# relay_board.net
KiCad netlist of a schematic drawn in EAGLE
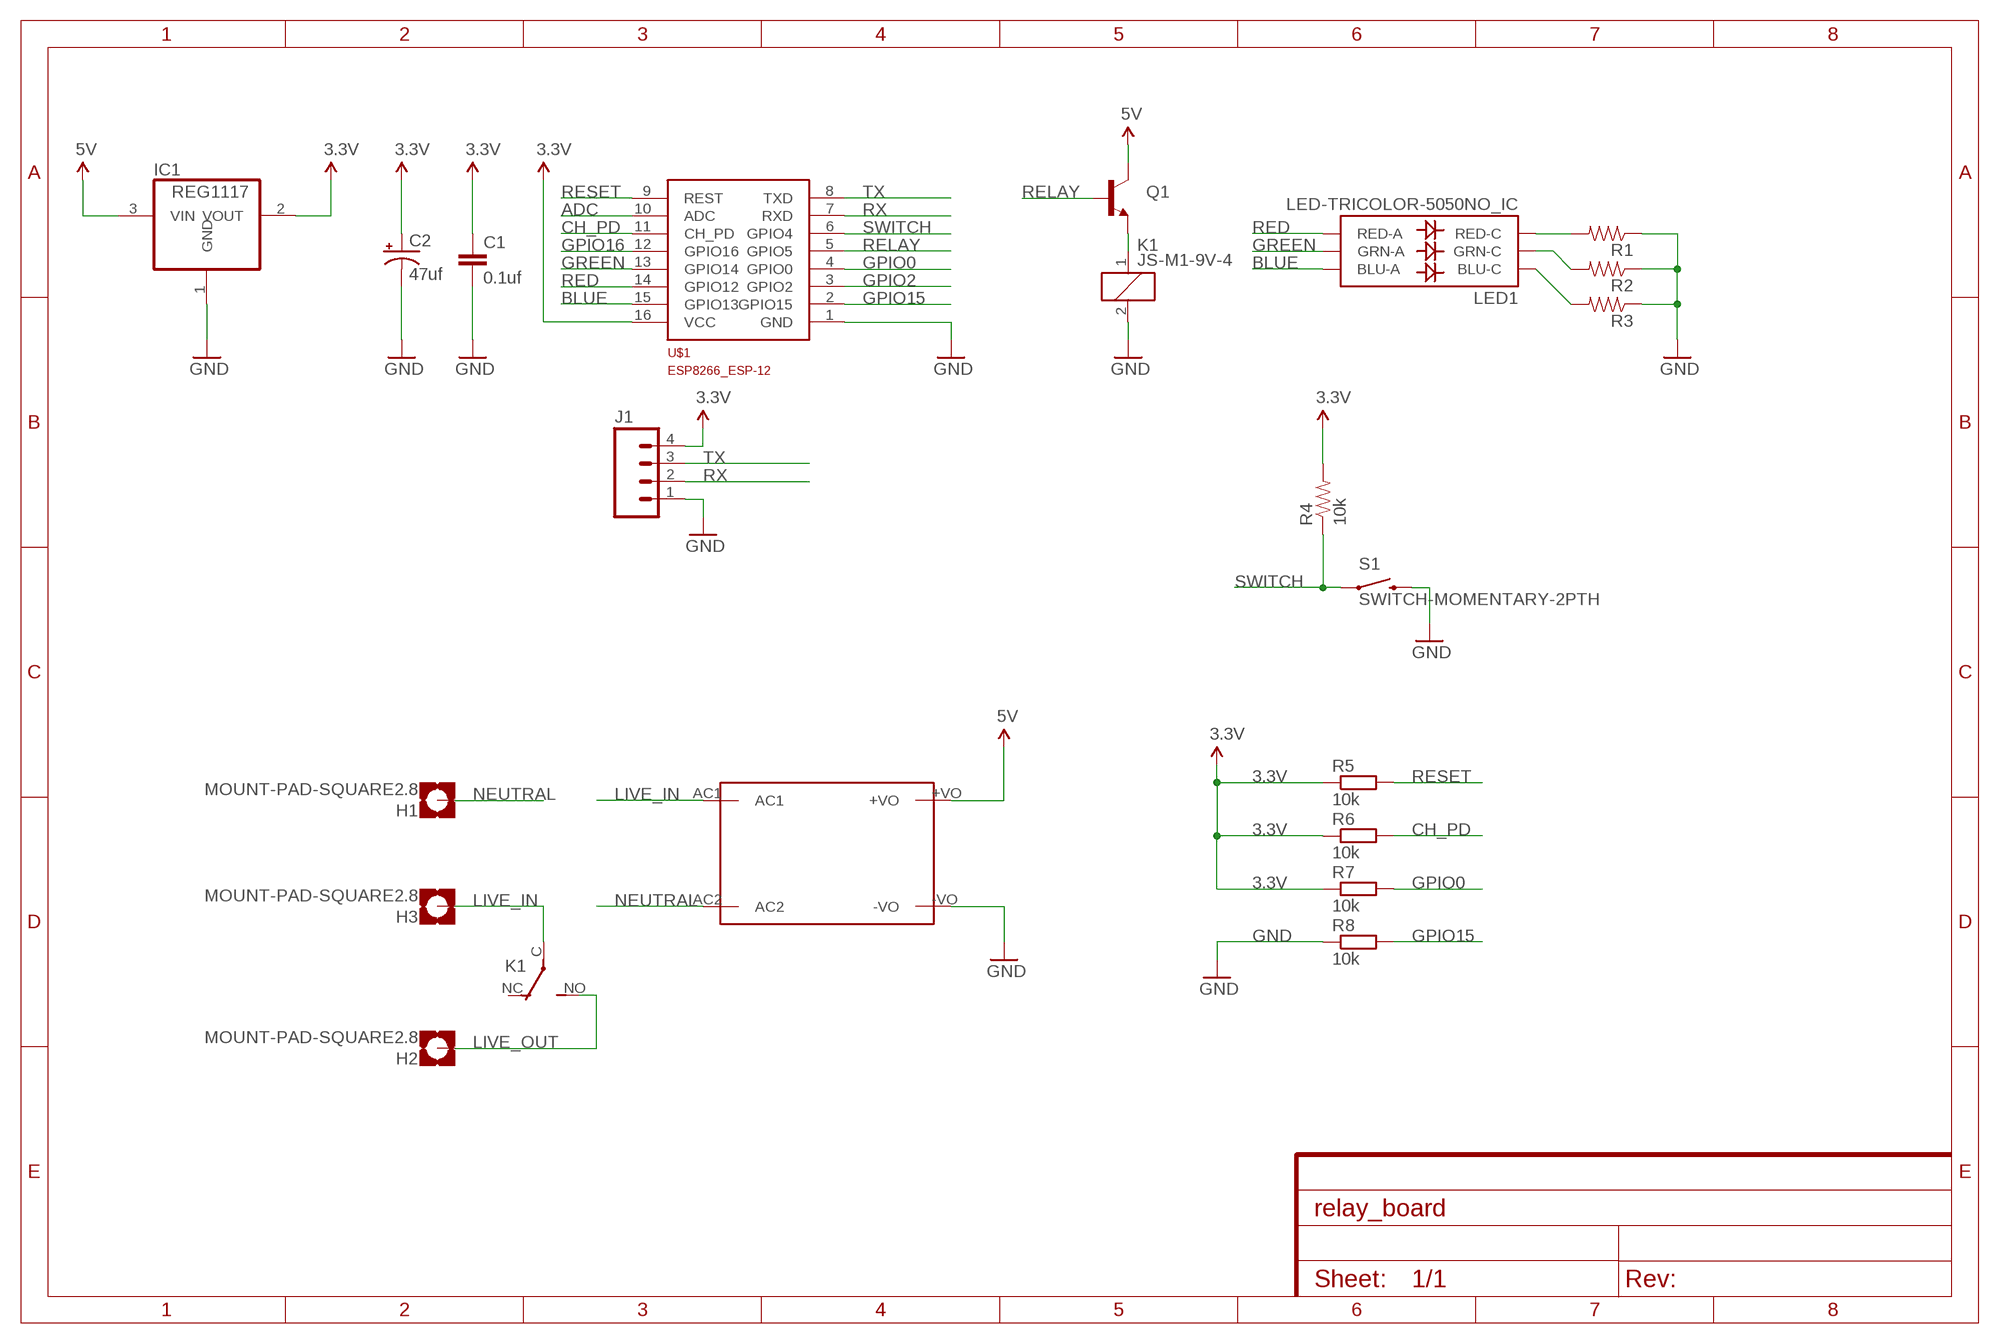
[diagram p0: schematic, sheet 1]

(export (version "E")
  (design (tool "Eeschema 10.0.6"))
  (components
    (comp (ref "C1")
      (value "0.1uf")
      (footprint "eagle-import:0805")
      (libsource (lib "eagle-import") (part "CAP0805"))
    )
    (comp (ref "C2")
      (value "47uf")
      (footprint "eagle-import:PANASONIC_E")
      (libsource (lib "eagle-import") (part "CAP_POLE"))
    )
    (comp (ref "H1")
      (value "MOUNT-PAD-SQUARE2.8")
      (footprint "eagle-import:2,8-PAD-SQUARE")
      (libsource (lib "eagle-import") (part "MOUNT-PAD-SQUARE2.8"))
    )
    (comp (ref "H2")
      (value "MOUNT-PAD-SQUARE2.8")
      (footprint "eagle-import:2,8-PAD-SQUARE")
      (libsource (lib "eagle-import") (part "MOUNT-PAD-SQUARE2.8"))
    )
    (comp (ref "H3")
      (value "MOUNT-PAD-SQUARE2.8")
      (footprint "eagle-import:2,8-PAD-SQUARE")
      (libsource (lib "eagle-import") (part "MOUNT-PAD-SQUARE2.8"))
    )
    (comp (ref "IC1")
      (value "REG1117")
      (footprint "eagle-import:SOT223")
      (libsource (lib "eagle-import") (part "REG1117"))
    )
    (comp (ref "J1")
      (value "M04LOCK")
      (footprint "eagle-import:1X04_LOCK")
      (libsource (lib "eagle-import") (part "M04LOCK"))
    )
    (comp (ref "K1")
      (value "JS-M1-9V-4")
      (footprint "eagle-import:JS-M")
      (libsource (lib "eagle-import") (part "JS-M1-9V-4"))
    )
    (comp (ref "LED1")
      (value "LED-TRICOLOR-5050NO_IC")
      (footprint "eagle-import:LED-TRICOLOR-5050")
      (libsource (lib "eagle-import") (part "LED-TRICOLOR-5050NO_IC"))
    )
    (comp (ref "Q1")
      (value "TRANSISTOR_NPNSMD2")
      (footprint "eagle-import:SOT223")
      (libsource (lib "eagle-import") (part "TRANSISTOR_NPNSMD2"))
    )
    (comp (ref "R1")
      (value "RESISTOR0805-RES")
      (footprint "eagle-import:0805")
      (libsource (lib "eagle-import") (part "RESISTOR0805-RES"))
    )
    (comp (ref "R2")
      (value "RESISTOR0805-RES")
      (footprint "eagle-import:0805")
      (libsource (lib "eagle-import") (part "RESISTOR0805-RES"))
    )
    (comp (ref "R3")
      (value "RESISTOR0805-RES")
      (footprint "eagle-import:0805")
      (libsource (lib "eagle-import") (part "RESISTOR0805-RES"))
    )
    (comp (ref "R4")
      (value "10k")
      (footprint "eagle-import:0805")
      (libsource (lib "eagle-import") (part "RESISTOR0805-RES"))
    )
    (comp (ref "R5")
      (value "10k")
      (footprint "eagle-import:R0805")
      (libsource (lib "eagle-import") (part "R-EU_R0805"))
    )
    (comp (ref "R6")
      (value "10k")
      (footprint "eagle-import:R0805")
      (libsource (lib "eagle-import") (part "R-EU_R0805"))
    )
    (comp (ref "R7")
      (value "10k")
      (footprint "eagle-import:R0805")
      (libsource (lib "eagle-import") (part "R-EU_R0805"))
    )
    (comp (ref "R8")
      (value "10k")
      (footprint "eagle-import:R0805")
      (libsource (lib "eagle-import") (part "R-EU_R0805"))
    )
    (comp (ref "S1")
      (value "SWITCH-MOMENTARY-2PTH")
      (footprint "eagle-import:TACTILE-PTH")
      (libsource (lib "eagle-import") (part "SWITCH-MOMENTARY-2PTH"))
    )
    (comp (ref "U$1")
      (value "ESP8266_ESP-12")
      (footprint "eagle-import:ESP8266-ESP12")
      (libsource (lib "eagle-import") (part "ESP8266_ESP-12"))
    )
    (comp (ref "U$2")
      (value "HLK-PM03")
      (footprint "eagle-import:HLK-PM03")
      (libsource (lib "eagle-import") (part "HLK-PM03"))
    )
  )
  (nets
    (net (code "1") (name "/ADC") (class "Default")
      (node (ref "U$1") (pin "10") (pinfunction "ADC_10") (pintype "bidirectional"))
    )
    (net (code "2") (name "/BLUE") (class "Default")
      (node (ref "LED1") (pin "3") (pinfunction "BLU-A_3") (pintype "bidirectional"))
      (node (ref "U$1") (pin "15") (pinfunction "GPIO13_15") (pintype "bidirectional"))
    )
    (net (code "3") (name "/CH_PD") (class "Default")
      (node (ref "R6") (pin "2") (pinfunction "2_2") (pintype "passive"))
      (node (ref "U$1") (pin "11") (pinfunction "CH_PD_11") (pintype "bidirectional"))
    )
    (net (code "4") (name "/GPIO0") (class "Default")
      (node (ref "R7") (pin "2") (pinfunction "2_2") (pintype "passive"))
      (node (ref "U$1") (pin "4") (pinfunction "GPIO0_4") (pintype "bidirectional"))
    )
    (net (code "5") (name "/GPIO2") (class "Default")
      (node (ref "U$1") (pin "3") (pinfunction "GPIO2_3") (pintype "bidirectional"))
    )
    (net (code "6") (name "/GPIO15") (class "Default")
      (node (ref "R8") (pin "2") (pinfunction "2_2") (pintype "passive"))
      (node (ref "U$1") (pin "2") (pinfunction "GPIO15_2") (pintype "bidirectional"))
    )
    (net (code "7") (name "/GPIO16") (class "Default")
      (node (ref "U$1") (pin "12") (pinfunction "GPIO16_12") (pintype "bidirectional"))
    )
    (net (code "8") (name "/GREEN") (class "Default")
      (node (ref "LED1") (pin "1") (pinfunction "GRN-A_1") (pintype "bidirectional"))
      (node (ref "U$1") (pin "13") (pinfunction "GPIO14_13") (pintype "bidirectional"))
    )
    (net (code "9") (name "/LIVE_IN") (class "Default")
      (node (ref "H3") (pin "B2,8") (pinfunction "MOUNT_B2,8") (pintype "passive"))
      (node (ref "K1") (pin "C") (pinfunction "P_C") (pintype "passive"))
      (node (ref "U$2") (pin "AC1") (pinfunction "AC1_AC1") (pintype "bidirectional"))
    )
    (net (code "10") (name "/LIVE_OUT") (class "Default")
      (node (ref "H2") (pin "B2,8") (pinfunction "MOUNT_B2,8") (pintype "passive"))
      (node (ref "K1") (pin "NO") (pinfunction "S_NO") (pintype "passive"))
    )
    (net (code "11") (name "/NEUTRAL") (class "Default")
      (node (ref "H1") (pin "B2,8") (pinfunction "MOUNT_B2,8") (pintype "passive"))
      (node (ref "U$2") (pin "AC2") (pinfunction "AC2_AC2") (pintype "bidirectional"))
    )
    (net (code "12") (name "/RED") (class "Default")
      (node (ref "LED1") (pin "2") (pinfunction "RED-A_2") (pintype "bidirectional"))
      (node (ref "U$1") (pin "14") (pinfunction "GPIO12_14") (pintype "bidirectional"))
    )
    (net (code "13") (name "/RELAY") (class "Default")
      (node (ref "Q1") (pin "1") (pinfunction "B_1") (pintype "passive"))
      (node (ref "U$1") (pin "5") (pinfunction "GPIO5_5") (pintype "bidirectional"))
    )
    (net (code "14") (name "/RESET") (class "Default")
      (node (ref "R5") (pin "2") (pinfunction "2_2") (pintype "passive"))
      (node (ref "U$1") (pin "9") (pinfunction "REST_9") (pintype "bidirectional"))
    )
    (net (code "15") (name "/RX") (class "Default")
      (node (ref "J1") (pin "2") (pinfunction "2_2") (pintype "passive"))
      (node (ref "U$1") (pin "7") (pinfunction "RXD_7") (pintype "bidirectional"))
    )
    (net (code "16") (name "/SWITCH") (class "Default")
      (node (ref "R4") (pin "1") (pinfunction "1_1") (pintype "passive"))
      (node (ref "S1") (pin "1") (pinfunction "1_1") (pintype "passive"))
      (node (ref "U$1") (pin "6") (pinfunction "GPIO4_6") (pintype "bidirectional"))
    )
    (net (code "17") (name "/TX") (class "Default")
      (node (ref "J1") (pin "3") (pinfunction "3_3") (pintype "passive"))
      (node (ref "U$1") (pin "8") (pinfunction "TXD_8") (pintype "bidirectional"))
    )
    (net (code "18") (name "3.3V") (class "Default")
      (node (ref "C1") (pin "1") (pinfunction "1_1") (pintype "passive"))
      (node (ref "C2") (pin "+") (pinfunction "+_+") (pintype "passive"))
      (node (ref "IC1") (pin "2") (pinfunction "VOUT_2") (pintype "output"))
      (node (ref "J1") (pin "4") (pinfunction "4_4") (pintype "passive"))
      (node (ref "R4") (pin "2") (pinfunction "2_2") (pintype "passive"))
      (node (ref "R5") (pin "1") (pinfunction "1_1") (pintype "passive"))
      (node (ref "R6") (pin "1") (pinfunction "1_1") (pintype "passive"))
      (node (ref "R7") (pin "1") (pinfunction "1_1") (pintype "passive"))
      (node (ref "U$1") (pin "16") (pinfunction "VCC_16") (pintype "bidirectional"))
    )
    (net (code "19") (name "5V") (class "Default")
      (node (ref "IC1") (pin "3") (pinfunction "VIN_3") (pintype "input"))
      (node (ref "Q1") (pin "2") (pinfunction "C_2") (pintype "passive"))
      (node (ref "U$2") (pin "+VO") (pinfunction "+VO_+VO") (pintype "bidirectional"))
    )
    (net (code "20") (name "GND") (class "Default")
      (node (ref "C1") (pin "2") (pinfunction "2_2") (pintype "passive"))
      (node (ref "C2") (pin "-") (pinfunction "-_-") (pintype "passive"))
      (node (ref "IC1") (pin "1") (pinfunction "GND_1") (pintype "power_in"))
      (node (ref "J1") (pin "1") (pinfunction "1_1") (pintype "passive"))
      (node (ref "K1") (pin "2") (pinfunction "2_2") (pintype "passive"))
      (node (ref "R1") (pin "1") (pinfunction "1_1") (pintype "passive"))
      (node (ref "R2") (pin "1") (pinfunction "1_1") (pintype "passive"))
      (node (ref "R3") (pin "1") (pinfunction "1_1") (pintype "passive"))
      (node (ref "R8") (pin "1") (pinfunction "1_1") (pintype "passive"))
      (node (ref "S1") (pin "3") (pinfunction "2_3") (pintype "passive"))
      (node (ref "U$1") (pin "1") (pinfunction "GND_1") (pintype "bidirectional"))
      (node (ref "U$2") (pin "-VO") (pinfunction "-VO_-VO") (pintype "bidirectional"))
    )
    (net (code "21") (name "Net-(LED1-BLU-C)") (class "Default")
      (node (ref "LED1") (pin "4") (pinfunction "BLU-C_4") (pintype "bidirectional"))
      (node (ref "R3") (pin "2") (pinfunction "2_2") (pintype "passive"))
    )
    (net (code "22") (name "Net-(LED1-GRN-C)") (class "Default")
      (node (ref "LED1") (pin "6") (pinfunction "GRN-C_6") (pintype "bidirectional"))
      (node (ref "R2") (pin "2") (pinfunction "2_2") (pintype "passive"))
    )
    (net (code "23") (name "Net-(LED1-RED-C)") (class "Default")
      (node (ref "LED1") (pin "5") (pinfunction "RED-C_5") (pintype "bidirectional"))
      (node (ref "R1") (pin "2") (pinfunction "2_2") (pintype "passive"))
    )
    (net (code "24") (name "Net-(Q1-E)") (class "Default")
      (node (ref "K1") (pin "1") (pinfunction "1_1") (pintype "passive"))
      (node (ref "Q1") (pin "3") (pinfunction "E_3") (pintype "passive"))
    )
    (net (code "25") (name "unconnected-(K1B-O-PadNC)") (class "Default")
      (node (ref "K1") (pin "NC") (pinfunction "O_NC") (pintype "passive"))
    )
  )
)
